# Sheet1.net
KiCad netlist of a schematic drawn in Altium Designer
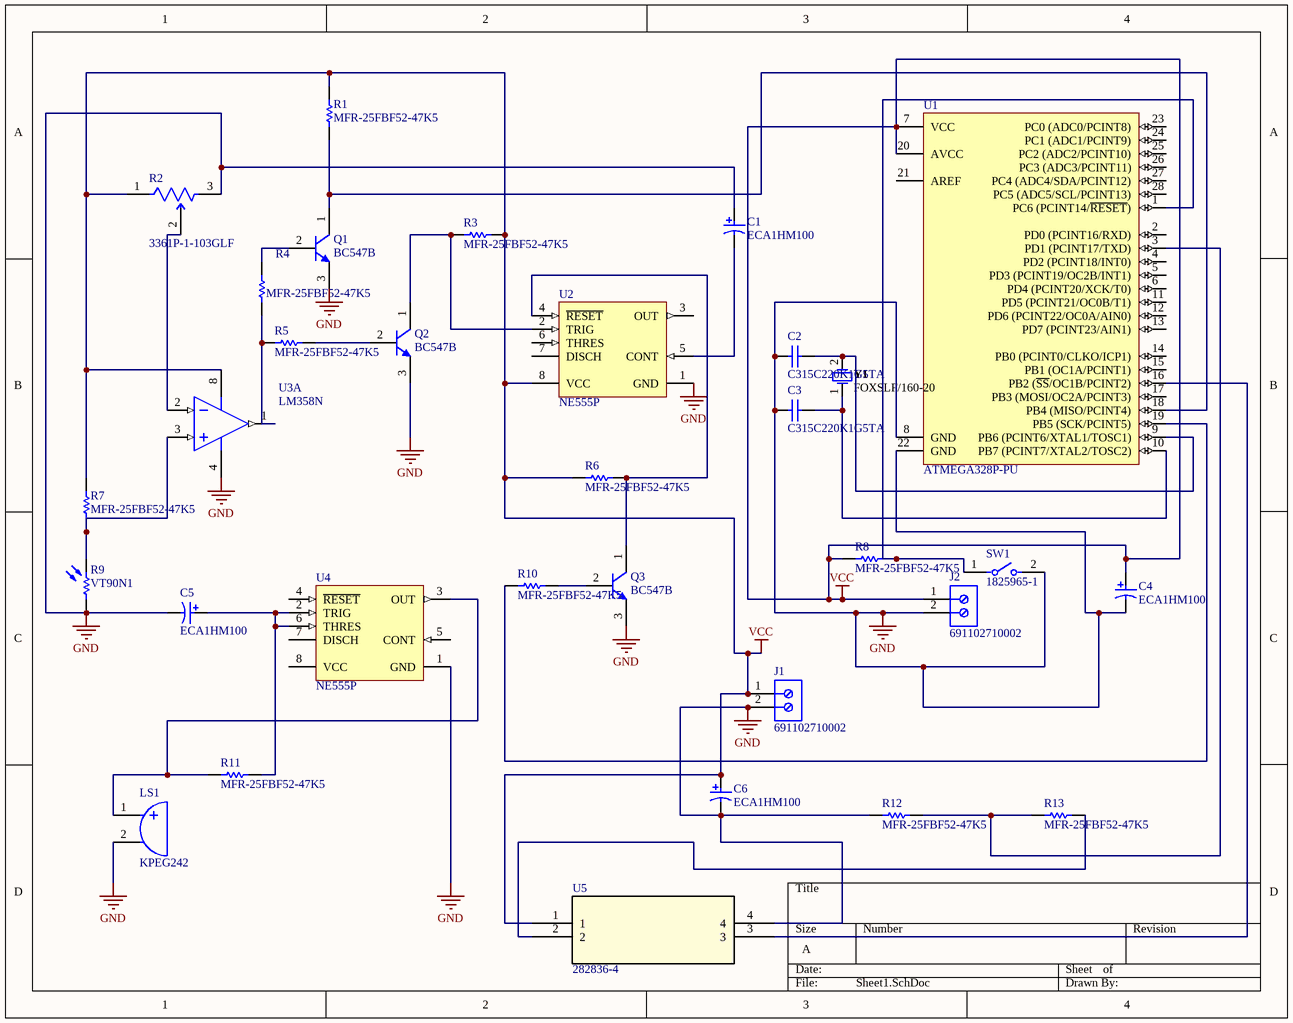
[diagram p0: Sheet1.SchDoc]

(export (version "E")
  (design (tool "Eeschema 10.0.6"))
  (components
    (comp (ref "C1")
      (value "ECA1HM100")
      (footprint "CAPPR55-200-1100X500X1200")
      (description "Aluminum Electrolytic Capacitor, 10 uF, +/- 20%, 50 V, -40 to 85 degC, 2-Pin THD, RoHS, Bulk")
      (fields (field (name "MANUFACTURER") "Panasonic") (field (name "TOLERANCE") "20%"))
      (libsource (lib "Altium Content Vault") (part "CAP-P-2"))
    )
    (comp (ref "C2")
      (value "C315C220K1G5TA")
      (footprint "KEMT-C315-THT-2")
      (description "Capacitor, Ceramic, 22 pF, +/-10 %, 100 V, -55 to 125 degC, 2-Pin THD, RoHS, Bulk")
      (libsource (lib "Altium Content Vault") (part "CAP-NP-2"))
    )
    (comp (ref "C3")
      (value "C315C220K1G5TA")
      (footprint "KEMT-C315-THT-2")
      (description "Capacitor, Ceramic, 22 pF, +/-10 %, 100 V, -55 to 125 degC, 2-Pin THD, RoHS, Bulk")
      (libsource (lib "Altium Content Vault") (part "CAP-NP-2"))
    )
    (comp (ref "C4")
      (value "ECA1HM100")
      (footprint "CAPPR55-200-1100X500X1200")
      (description "Aluminum Electrolytic Capacitor, 10 uF, +/- 20%, 50 V, -40 to 85 degC, 2-Pin THD, RoHS, Bulk")
      (fields (field (name "MANUFACTURER") "Panasonic") (field (name "TOLERANCE") "20%"))
      (libsource (lib "Altium Content Vault") (part "CAP-P-2"))
    )
    (comp (ref "C5")
      (value "ECA1HM100")
      (footprint "CAPPR55-200-1100X500X1200")
      (description "Aluminum Electrolytic Capacitor, 10 uF, +/- 20%, 50 V, -40 to 85 degC, 2-Pin THD, RoHS, Bulk")
      (fields (field (name "MANUFACTURER") "Panasonic") (field (name "TOLERANCE") "20%"))
      (libsource (lib "Altium Content Vault") (part "CAP-P-2"))
    )
    (comp (ref "C6")
      (value "ECA1HM100")
      (footprint "CAPPR55-200-1100X500X1200")
      (description "Aluminum Electrolytic Capacitor, 10 uF, +/- 20%, 50 V, -40 to 85 degC, 2-Pin THD, RoHS, Bulk")
      (fields (field (name "MANUFACTURER") "Panasonic") (field (name "TOLERANCE") "20%"))
      (libsource (lib "Altium Content Vault") (part "CAP-P-2"))
    )
    (comp (ref "J1")
      (value "691102710002")
      (footprint "691102710002")
      (description "Series 102 - 5.00 mm Horizontal Entry Modular with Pressure Clamp WR-TBL, 2 pin")
      (fields (field (name "MANUFACTURER") "Wurth Elektronik") (field (name "PUBLISHER") "WurthElektronik"))
      (libsource (lib "Altium Content Vault") (part "WE-CN-1P-F-TB2"))
    )
    (comp (ref "J2")
      (value "691102710002")
      (footprint "691102710002")
      (description "Series 102 - 5.00 mm Horizontal Entry Modular with Pressure Clamp WR-TBL, 2 pin")
      (fields (field (name "MANUFACTURER") "Wurth Elektronik") (field (name "PUBLISHER") "WurthElektronik"))
      (libsource (lib "Altium Content Vault") (part "WE-CN-1P-F-TB2"))
    )
    (comp (ref "LS1")
      (value "KPEG242")
      (footprint "KINGS-KPEG242-2")
      (description "Piezo Indicator, 4100 Hz, 3 to 16 V, -20 to 70 degC, 2-Pin THD, RoHS")
      (fields (field (name "PARTNUMBER") "KPE-242") (field (name "MANUFACTURER") "KingstateElectronicsCorp."))
      (libsource (lib "Altium Content Vault") (part "KINGS-KPEG242-2"))
    )
    (comp (ref "Q1")
      (value "BC547B")
      (footprint "ONSC-TO-92-3-29-11")
      (description "Amplifier Transistor, NPN Silicon, 3-Pin TO-92, Bulk Box")
      (fields (field (name "MANUFACTURER") "On Semiconductor"))
      (libsource (lib "Altium Content Vault") (part "ONSC-NPN-C1B2E3-3"))
    )
    (comp (ref "Q2")
      (value "BC547B")
      (footprint "ONSC-TO-92-3-29-11")
      (description "Amplifier Transistor, NPN Silicon, 3-Pin TO-92, Bulk Box")
      (fields (field (name "MANUFACTURER") "On Semiconductor"))
      (libsource (lib "Altium Content Vault") (part "ONSC-NPN-C1B2E3-3"))
    )
    (comp (ref "Q3")
      (value "BC547B")
      (footprint "ONSC-TO-92-3-29-11")
      (description "Amplifier Transistor, NPN Silicon, 3-Pin TO-92, Bulk Box")
      (fields (field (name "MANUFACTURER") "On Semiconductor"))
      (libsource (lib "Altium Content Vault") (part "ONSC-NPN-C1B2E3-3"))
    )
    (comp (ref "R1")
      (value "MFR-25FBF52-47K5")
      (footprint "RESA60-630X240")
      (description "Axial Resistor, 47.5 KOhm, +/- 1%, 0.25 W, -55 to 155 degC, 2-Pin THD, RoHS, Bulk")
      (fields (field (name "TOLERANCE") "20%"))
      (libsource (lib "Altium Content Vault") (part "RES-2"))
    )
    (comp (ref "R2")
      (value "3361P-1-103GLF")
      (footprint "FP-3361P-MFG")
      (description "TRIMMER 10K OHM 0.5W GW TOP ADJ")
      (fields (field (name "TOLERANCE") "10%"))
      (libsource (lib "Altium Content Vault") (part "2dcfd2547301a7d3209a5e99acfd772"))
    )
    (comp (ref "R3")
      (value "MFR-25FBF52-47K5")
      (footprint "RESA60-630X240")
      (description "Axial Resistor, 47.5 KOhm, +/- 1%, 0.25 W, -55 to 155 degC, 2-Pin THD, RoHS, Bulk")
      (fields (field (name "TOLERANCE") "20%"))
      (libsource (lib "Altium Content Vault") (part "RES-2"))
    )
    (comp (ref "R4")
      (value "MFR-25FBF52-47K5")
      (footprint "RESA60-630X240")
      (description "Axial Resistor, 47.5 KOhm, +/- 1%, 0.25 W, -55 to 155 degC, 2-Pin THD, RoHS, Bulk")
      (fields (field (name "TOLERANCE") "20%"))
      (libsource (lib "Altium Content Vault") (part "RES-2"))
    )
    (comp (ref "R5")
      (value "MFR-25FBF52-47K5")
      (footprint "RESA60-630X240")
      (description "Axial Resistor, 47.5 KOhm, +/- 1%, 0.25 W, -55 to 155 degC, 2-Pin THD, RoHS, Bulk")
      (fields (field (name "TOLERANCE") "20%"))
      (libsource (lib "Altium Content Vault") (part "RES-2"))
    )
    (comp (ref "R6")
      (value "MFR-25FBF52-47K5")
      (footprint "RESA60-630X240")
      (description "Axial Resistor, 47.5 KOhm, +/- 1%, 0.25 W, -55 to 155 degC, 2-Pin THD, RoHS, Bulk")
      (fields (field (name "TOLERANCE") "20%"))
      (libsource (lib "Altium Content Vault") (part "RES-2"))
    )
    (comp (ref "R7")
      (value "MFR-25FBF52-47K5")
      (footprint "RESA60-630X240")
      (description "Axial Resistor, 47.5 KOhm, +/- 1%, 0.25 W, -55 to 155 degC, 2-Pin THD, RoHS, Bulk")
      (fields (field (name "TOLERANCE") "20%"))
      (libsource (lib "Altium Content Vault") (part "RES-2"))
    )
    (comp (ref "R8")
      (value "MFR-25FBF52-47K5")
      (footprint "RESA60-630X240")
      (description "Axial Resistor, 47.5 KOhm, +/- 1%, 0.25 W, -55 to 155 degC, 2-Pin THD, RoHS, Bulk")
      (fields (field (name "TOLERANCE") "20%"))
      (libsource (lib "Altium Content Vault") (part "RES-2"))
    )
    (comp (ref "R9")
      (value "VT90N1")
      (footprint "EXCE-VT90N1")
      (description "Photoconductive Resistor, 200 kOhm, 100 V, 80 mW, -40 to 75 degC, 2-Pin THD, RoHS")
      (fields (field (name "MANUFACTURER") "Excelitas Technology"))
      (libsource (lib "Altium Content Vault") (part "PHOTO-RES-2"))
    )
    (comp (ref "R10")
      (value "MFR-25FBF52-47K5")
      (footprint "RESA60-630X240")
      (description "Axial Resistor, 47.5 KOhm, +/- 1%, 0.25 W, -55 to 155 degC, 2-Pin THD, RoHS, Bulk")
      (fields (field (name "TOLERANCE") "20%"))
      (libsource (lib "Altium Content Vault") (part "RES-2"))
    )
    (comp (ref "R11")
      (value "MFR-25FBF52-47K5")
      (footprint "RESA60-630X240")
      (description "Axial Resistor, 47.5 KOhm, +/- 1%, 0.25 W, -55 to 155 degC, 2-Pin THD, RoHS, Bulk")
      (fields (field (name "TOLERANCE") "20%"))
      (libsource (lib "Altium Content Vault") (part "RES-2"))
    )
    (comp (ref "R12")
      (value "MFR-25FBF52-47K5")
      (footprint "RESA60-630X240")
      (description "Axial Resistor, 47.5 KOhm, +/- 1%, 0.25 W, -55 to 155 degC, 2-Pin THD, RoHS, Bulk")
      (fields (field (name "TOLERANCE") "20%"))
      (libsource (lib "Altium Content Vault") (part "RES-2"))
    )
    (comp (ref "R13")
      (value "MFR-25FBF52-47K5")
      (footprint "RESA60-630X240")
      (description "Axial Resistor, 47.5 KOhm, +/- 1%, 0.25 W, -55 to 155 degC, 2-Pin THD, RoHS, Bulk")
      (fields (field (name "TOLERANCE") "20%"))
      (libsource (lib "Altium Content Vault") (part "RES-2"))
    )
    (comp (ref "SW1")
      (value "1825965-1")
      (footprint "FP-1825965-1-MFG")
      (description "SWITCH TACTILE SPST-NO 0.05A 24V")
      (libsource (lib "Altium Content Vault") (part "bb27bde45df87f1f469753f287ef5ae"))
    )
    (comp (ref "U1")
      (value "ATMEGA328P-PU")
      (footprint "ATML-28P3")
      (fields (field (name "MANUFACTURER") "Atmel"))
      (libsource (lib "University of Moratuwa") (part "MC-8B-ATM48-IL28"))
    )
    (comp (ref "U2")
      (value "NE555P")
      (footprint "P0008A")
      (description "Precision Timer, 4.5 to 16 V, 0 to 70 degC, 8-Pin DIP, Pb-Free, Tube")
      (fields (field (name "MANUFACTURER") "TexasInstruments"))
      (libsource (lib "Altium Content Vault") (part "TI-NE555-P8"))
    )
    (comp (ref "U3")
      (value "LM358N")
      (footprint "ONSC-PDIP-8-626-05_M")
      (description "Single Supply Dual Operational Amplifier, 3 to 32 V, 0 to 70 degC, 8-Pin PDIP, Tube")
      (fields (field (name "MANUFACTURER") "On Semiconductor"))
      (libsource (lib "Altium Content Vault") (part "ONSC-LM358_NCV2904-8"))
    )
    (comp (ref "U4")
      (value "NE555P")
      (footprint "P0008A")
      (description "Precision Timer, 4.5 to 16 V, 0 to 70 degC, 8-Pin DIP, Pb-Free, Tube")
      (fields (field (name "MANUFACTURER") "TexasInstruments"))
      (libsource (lib "Altium Content Vault") (part "TI-NE555-P8"))
    )
    (comp (ref "U5")
      (value "282836-4")
      (footprint "282836-4_TYC")
      (description "No Description Available")
      (libsource (lib "282836-4") (part "282836-4"))
    )
    (comp (ref "Y1")
      (value "FOXSLF/160-20")
      (footprint "FOX-FOXSLF160-20")
      (description "Resistance Weld Thru-Hole Crystal, 16 MHz, -20 to 70 degC, 2-Pin THD, RoHS, Bulk")
      (fields (field (name "TOLERANCE") "1%"))
      (libsource (lib "Altium Content Vault") (part "XTAL-1-2-2"))
    )
  )
  (nets
    (net (code "1") (name "GND") (class "Default")
      (node (ref "C1") (pin "1") (pinfunction "1_1") (pintype "passive"))
      (node (ref "C2") (pin "1") (pinfunction "1_1") (pintype "passive"))
      (node (ref "C3") (pin "1") (pinfunction "1_1") (pintype "passive"))
      (node (ref "C4") (pin "2") (pinfunction "2_2") (pintype "passive"))
      (node (ref "C5") (pin "2") (pinfunction "2_2") (pintype "passive"))
      (node (ref "C6") (pin "2") (pinfunction "2_2") (pintype "passive"))
      (node (ref "J1") (pin "2") (pinfunction "GND_2") (pintype "passive"))
      (node (ref "J2") (pin "2") (pinfunction "GND_2") (pintype "passive"))
      (node (ref "LS1") (pin "2") (pinfunction "2_2") (pintype "passive"))
      (node (ref "Q1") (pin "3") (pinfunction "E_3") (pintype "passive"))
      (node (ref "Q2") (pin "3") (pinfunction "E_3") (pintype "passive"))
      (node (ref "Q3") (pin "3") (pinfunction "E_3") (pintype "passive"))
      (node (ref "R12") (pin "1") (pinfunction "1_1") (pintype "passive"))
      (node (ref "R2") (pin "3") (pinfunction "CW_3") (pintype "passive"))
      (node (ref "R9") (pin "1") (pinfunction "1_1") (pintype "passive"))
      (node (ref "SW1") (pin "2") (pinfunction "2_2") (pintype "passive"))
      (node (ref "U1") (pin "22") (pinfunction "GND_22") (pintype "power_in"))
      (node (ref "U1") (pin "8") (pinfunction "GND_8") (pintype "power_in"))
      (node (ref "U2") (pin "1") (pinfunction "GND_1") (pintype "power_in"))
      (node (ref "U3") (pin "4") (pinfunction "VEE/GND_4") (pintype "power_in"))
      (node (ref "U4") (pin "1") (pinfunction "GND_1") (pintype "power_in"))
      (node (ref "U5") (pin "4") (pinfunction "4_4") (pintype "passive"))
    )
    (net (code "2") (name "Net-(Q1-B)") (class "Default")
      (node (ref "Q1") (pin "2") (pinfunction "B_2") (pintype "passive"))
      (node (ref "R4") (pin "2") (pinfunction "2_2") (pintype "passive"))
    )
    (net (code "3") (name "Net-(Q1-C)") (class "Default")
      (node (ref "Q1") (pin "1") (pinfunction "C_1") (pintype "passive"))
      (node (ref "R1") (pin "1") (pinfunction "1_1") (pintype "passive"))
      (node (ref "U1") (pin "18") (pinfunction "PB4_(MISO/PCINT4)_18") (pintype "bidirectional"))
    )
    (net (code "4") (name "Net-(Q2-B)") (class "Default")
      (node (ref "Q2") (pin "2") (pinfunction "B_2") (pintype "passive"))
      (node (ref "R5") (pin "2") (pinfunction "2_2") (pintype "passive"))
    )
    (net (code "5") (name "Net-(Q2-C)") (class "Default")
      (node (ref "Q2") (pin "1") (pinfunction "C_1") (pintype "passive"))
      (node (ref "R3") (pin "1") (pinfunction "1_1") (pintype "passive"))
      (node (ref "U2") (pin "2") (pinfunction "TRIG_2") (pintype "input"))
    )
    (net (code "6") (name "Net-(Q3-B)") (class "Default")
      (node (ref "Q3") (pin "2") (pinfunction "B_2") (pintype "passive"))
      (node (ref "R10") (pin "2") (pinfunction "2_2") (pintype "passive"))
    )
    (net (code "7") (name "Net-(Q3-C)") (class "Default")
      (node (ref "Q3") (pin "1") (pinfunction "C_1") (pintype "passive"))
      (node (ref "R6") (pin "2") (pinfunction "2_2") (pintype "passive"))
      (node (ref "U2") (pin "4") (pinfunction "~{RESET}_4") (pintype "input"))
    )
    (net (code "8") (name "Net-(R2-WIPER)") (class "Default")
      (node (ref "R2") (pin "2") (pinfunction "WIPER_2") (pintype "passive"))
      (node (ref "U3") (pin "2") (pinfunction "INA-_2") (pintype "input"))
    )
    (net (code "9") (name "Net-(R13-Pad2)") (class "Default")
      (node (ref "R13") (pin "2") (pinfunction "2_2") (pintype "passive"))
      (node (ref "U5") (pin "2") (pinfunction "2_2") (pintype "passive"))
    )
    (net (code "10") (name "Net-(U1-PB2_(~{SS}{slash}OC1B{slash}PCINT2))") (class "Default")
      (node (ref "U1") (pin "16") (pinfunction "PB2_(~{SS}/OC1B/PCINT2)_16") (pintype "bidirectional"))
      (node (ref "U5") (pin "3") (pinfunction "3_3") (pintype "passive"))
    )
    (net (code "11") (name "Net-(U1-PB5_(SCK{slash}PCINT5))") (class "Default")
      (node (ref "R10") (pin "1") (pinfunction "1_1") (pintype "passive"))
      (node (ref "U1") (pin "19") (pinfunction "PB5_(SCK/PCINT5)_19") (pintype "bidirectional"))
    )
    (net (code "12") (name "Net-(U1-PB6_(PCINT6{slash}XTAL1{slash}TOSC1))") (class "Default")
      (node (ref "C2") (pin "2") (pinfunction "2_2") (pintype "passive"))
      (node (ref "U1") (pin "9") (pinfunction "PB6_(PCINT6/XTAL1/TOSC1)_9") (pintype "bidirectional"))
      (node (ref "Y1") (pin "2") (pinfunction "2_2") (pintype "passive"))
    )
    (net (code "13") (name "Net-(U1-PB7_(PCINT7{slash}XTAL2{slash}TOSC2))") (class "Default")
      (node (ref "C3") (pin "2") (pinfunction "2_2") (pintype "passive"))
      (node (ref "U1") (pin "10") (pinfunction "PB7_(PCINT7/XTAL2/TOSC2)_10") (pintype "bidirectional"))
      (node (ref "Y1") (pin "1") (pinfunction "1_1") (pintype "passive"))
    )
    (net (code "14") (name "Net-(U1-PC6_(PCINT14{slash}~{RESET}))") (class "Default")
      (node (ref "R8") (pin "2") (pinfunction "2_2") (pintype "passive"))
      (node (ref "SW1") (pin "1") (pinfunction "1_1") (pintype "passive"))
      (node (ref "U1") (pin "1") (pinfunction "PC6_(PCINT14/~{RESET})_1") (pintype "bidirectional"))
    )
    (net (code "15") (name "Net-(U1-PD1_(PCINT17{slash}TXD))") (class "Default")
      (node (ref "R12") (pin "2") (pinfunction "2_2") (pintype "passive"))
      (node (ref "R13") (pin "1") (pinfunction "1_1") (pintype "passive"))
      (node (ref "U1") (pin "3") (pinfunction "PD1_(PCINT17/TXD)_3") (pintype "bidirectional"))
    )
    (net (code "16") (name "Net-(U2-CONT)") (class "Default")
      (node (ref "C1") (pin "2") (pinfunction "2_2") (pintype "passive"))
      (node (ref "U2") (pin "5") (pinfunction "CONT_5") (pintype "input"))
    )
    (net (code "17") (name "Net-(U3A-INA+)") (class "Default")
      (node (ref "R7") (pin "1") (pinfunction "1_1") (pintype "passive"))
      (node (ref "R9") (pin "2") (pinfunction "2_2") (pintype "passive"))
      (node (ref "U3") (pin "3") (pinfunction "INA+_3") (pintype "input"))
    )
    (net (code "18") (name "Net-(U3A-OUTA)") (class "Default")
      (node (ref "R4") (pin "1") (pinfunction "1_1") (pintype "passive"))
      (node (ref "R5") (pin "1") (pinfunction "1_1") (pintype "passive"))
      (node (ref "U3") (pin "1") (pinfunction "OUTA_1") (pintype "output"))
    )
    (net (code "19") (name "Net-(U4-OUT)") (class "Default")
      (node (ref "LS1") (pin "1") (pinfunction "1_1") (pintype "passive"))
      (node (ref "R11") (pin "1") (pinfunction "1_1") (pintype "passive"))
      (node (ref "U4") (pin "3") (pinfunction "OUT_3") (pintype "output"))
    )
    (net (code "20") (name "Net-(U4-THRES)") (class "Default")
      (node (ref "C5") (pin "1") (pinfunction "1_1") (pintype "passive"))
      (node (ref "R11") (pin "2") (pinfunction "2_2") (pintype "passive"))
      (node (ref "U4") (pin "2") (pinfunction "TRIG_2") (pintype "input"))
      (node (ref "U4") (pin "6") (pinfunction "THRES_6") (pintype "input"))
    )
    (net (code "21") (name "VCC") (class "Default")
      (node (ref "C4") (pin "1") (pinfunction "1_1") (pintype "passive"))
      (node (ref "C6") (pin "1") (pinfunction "1_1") (pintype "passive"))
      (node (ref "J1") (pin "1") (pinfunction "5V_1") (pintype "passive"))
      (node (ref "J2") (pin "1") (pinfunction "5V_1") (pintype "passive"))
      (node (ref "R1") (pin "2") (pinfunction "2_2") (pintype "passive"))
      (node (ref "R2") (pin "1") (pinfunction "CCW_1") (pintype "passive"))
      (node (ref "R3") (pin "2") (pinfunction "2_2") (pintype "passive"))
      (node (ref "R6") (pin "1") (pinfunction "1_1") (pintype "passive"))
      (node (ref "R7") (pin "2") (pinfunction "2_2") (pintype "passive"))
      (node (ref "R8") (pin "1") (pinfunction "1_1") (pintype "passive"))
      (node (ref "U1") (pin "20") (pinfunction "AVCC_20") (pintype "power_in"))
      (node (ref "U1") (pin "7") (pinfunction "VCC_7") (pintype "power_in"))
      (node (ref "U2") (pin "8") (pinfunction "VCC_8") (pintype "power_in"))
      (node (ref "U3") (pin "8") (pinfunction "VCC_8") (pintype "power_in"))
      (node (ref "U5") (pin "1") (pinfunction "1_1") (pintype "passive"))
    )
    (net (code "22") (name "unconnected-(U1-AREF-Pad21)") (class "Default")
      (node (ref "U1") (pin "21") (pinfunction "AREF_21") (pintype "power_in"))
    )
    (net (code "23") (name "unconnected-(U1-PB0_(PCINT0{slash}CLKO{slash}ICP1)-Pad14)") (class "Default")
      (node (ref "U1") (pin "14") (pinfunction "PB0_(PCINT0/CLKO/ICP1)_14") (pintype "bidirectional"))
    )
    (net (code "24") (name "unconnected-(U1-PB1_(OC1A{slash}PCINT1)-Pad15)") (class "Default")
      (node (ref "U1") (pin "15") (pinfunction "PB1_(OC1A/PCINT1)_15") (pintype "bidirectional"))
    )
    (net (code "25") (name "unconnected-(U1-PB3_(MOSI{slash}OC2A{slash}PCINT3)-Pad17)") (class "Default")
      (node (ref "U1") (pin "17") (pinfunction "PB3_(MOSI/OC2A/PCINT3)_17") (pintype "bidirectional"))
    )
    (net (code "26") (name "unconnected-(U1-PC0_(ADC0{slash}PCINT8)-Pad23)") (class "Default")
      (node (ref "U1") (pin "23") (pinfunction "PC0_(ADC0/PCINT8)_23") (pintype "bidirectional"))
    )
    (net (code "27") (name "unconnected-(U1-PC1_(ADC1{slash}PCINT9)-Pad24)") (class "Default")
      (node (ref "U1") (pin "24") (pinfunction "PC1_(ADC1/PCINT9)_24") (pintype "bidirectional"))
    )
    (net (code "28") (name "unconnected-(U1-PC2_(ADC2{slash}PCINT10)-Pad25)") (class "Default")
      (node (ref "U1") (pin "25") (pinfunction "PC2_(ADC2/PCINT10)_25") (pintype "bidirectional"))
    )
    (net (code "29") (name "unconnected-(U1-PC3_(ADC3{slash}PCINT11)-Pad26)") (class "Default")
      (node (ref "U1") (pin "26") (pinfunction "PC3_(ADC3/PCINT11)_26") (pintype "bidirectional"))
    )
    (net (code "30") (name "unconnected-(U1-PC4_(ADC4{slash}SDA{slash}PCINT12)-Pad27)") (class "Default")
      (node (ref "U1") (pin "27") (pinfunction "PC4_(ADC4/SDA/PCINT12)_27") (pintype "bidirectional"))
    )
    (net (code "31") (name "unconnected-(U1-PC5_(ADC5{slash}SCL{slash}PCINT13)-Pad28)") (class "Default")
      (node (ref "U1") (pin "28") (pinfunction "PC5_(ADC5/SCL/PCINT13)_28") (pintype "bidirectional"))
    )
    (net (code "32") (name "unconnected-(U1-PD0_(PCINT16{slash}RXD)-Pad2)") (class "Default")
      (node (ref "U1") (pin "2") (pinfunction "PD0_(PCINT16/RXD)_2") (pintype "bidirectional"))
    )
    (net (code "33") (name "unconnected-(U1-PD2_(PCINT18{slash}INT0)-Pad4)") (class "Default")
      (node (ref "U1") (pin "4") (pinfunction "PD2_(PCINT18/INT0)_4") (pintype "bidirectional"))
    )
    (net (code "34") (name "unconnected-(U1-PD3_(PCINT19{slash}OC2B{slash}INT1)-Pad5)") (class "Default")
      (node (ref "U1") (pin "5") (pinfunction "PD3_(PCINT19/OC2B/INT1)_5") (pintype "bidirectional"))
    )
    (net (code "35") (name "unconnected-(U1-PD4_(PCINT20{slash}XCK{slash}T0)-Pad6)") (class "Default")
      (node (ref "U1") (pin "6") (pinfunction "PD4_(PCINT20/XCK/T0)_6") (pintype "bidirectional"))
    )
    (net (code "36") (name "unconnected-(U1-PD5_(PCINT21{slash}OC0B{slash}T1)-Pad11)") (class "Default")
      (node (ref "U1") (pin "11") (pinfunction "PD5_(PCINT21/OC0B/T1)_11") (pintype "bidirectional"))
    )
    (net (code "37") (name "unconnected-(U1-PD6_(PCINT22{slash}OC0A{slash}AIN0)-Pad12)") (class "Default")
      (node (ref "U1") (pin "12") (pinfunction "PD6_(PCINT22/OC0A/AIN0)_12") (pintype "bidirectional"))
    )
    (net (code "38") (name "unconnected-(U1-PD7_(PCINT23{slash}AIN1)-Pad13)") (class "Default")
      (node (ref "U1") (pin "13") (pinfunction "PD7_(PCINT23/AIN1)_13") (pintype "bidirectional"))
    )
    (net (code "39") (name "unconnected-(U2-DISCH-Pad7)") (class "Default")
      (node (ref "U2") (pin "7") (pinfunction "DISCH_7") (pintype "open_collector"))
    )
    (net (code "40") (name "unconnected-(U2-OUT-Pad3)") (class "Default")
      (node (ref "U2") (pin "3") (pinfunction "OUT_3") (pintype "output"))
    )
    (net (code "41") (name "unconnected-(U2-THRES-Pad6)") (class "Default")
      (node (ref "U2") (pin "6") (pinfunction "THRES_6") (pintype "input"))
    )
    (net (code "42") (name "unconnected-(U4-CONT-Pad5)") (class "Default")
      (node (ref "U4") (pin "5") (pinfunction "CONT_5") (pintype "input"))
    )
    (net (code "43") (name "unconnected-(U4-DISCH-Pad7)") (class "Default")
      (node (ref "U4") (pin "7") (pinfunction "DISCH_7") (pintype "open_collector"))
    )
    (net (code "44") (name "unconnected-(U4-VCC-Pad8)") (class "Default")
      (node (ref "U4") (pin "8") (pinfunction "VCC_8") (pintype "power_in"))
    )
    (net (code "45") (name "unconnected-(U4-~{RESET}-Pad4)") (class "Default")
      (node (ref "U4") (pin "4") (pinfunction "~{RESET}_4") (pintype "input"))
    )
  )
)
